# VHDCI.net
KiCad netlist of a schematic drawn in Altium Designer
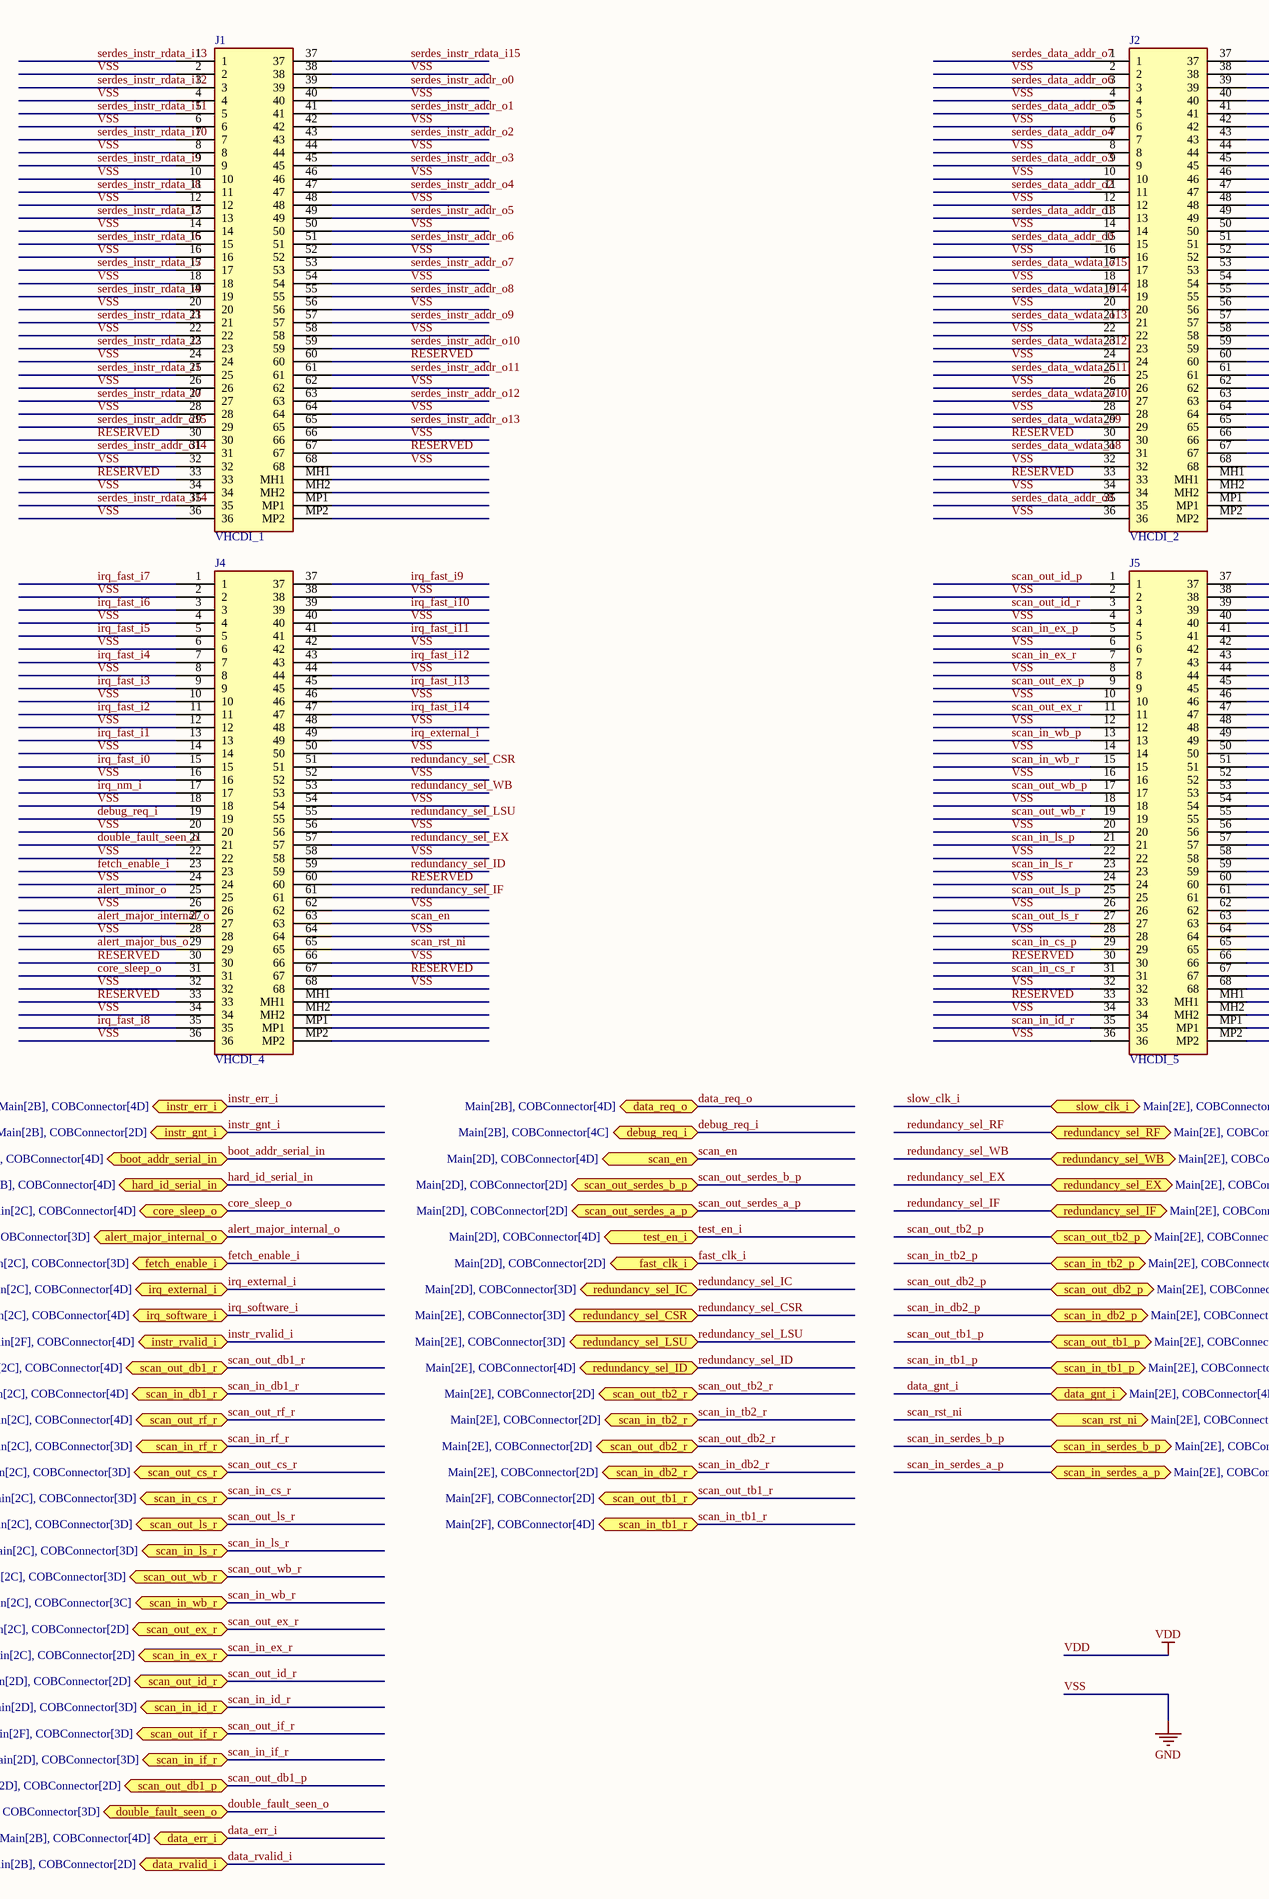
[diagram p0: VHDCI.SchDoc, left]
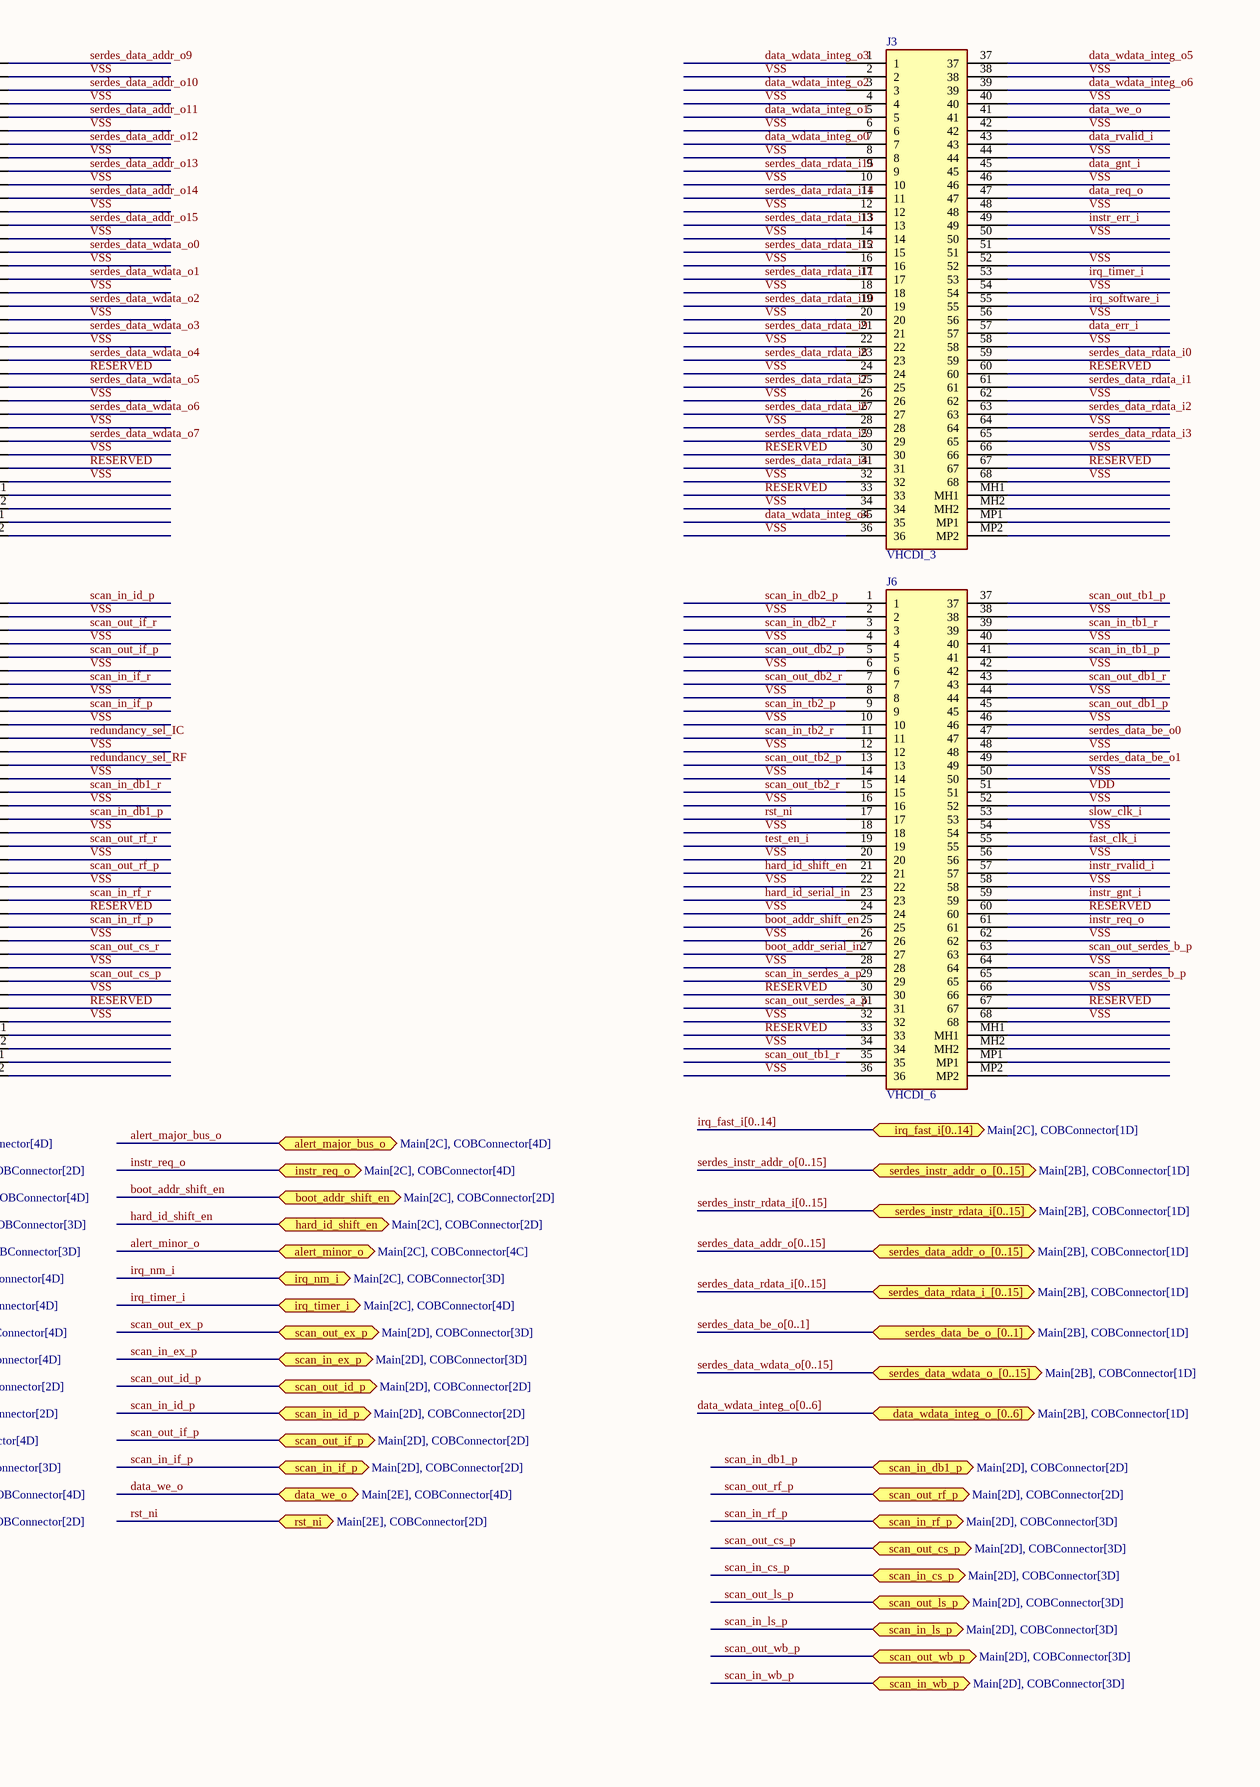
[diagram p1: VHDCI.SchDoc, right]

(export (version "E")
  (design (tool "Eeschema 10.0.6"))
  (components
    (comp (ref "J1")
      (value "VHCDI_1")
      (footprint "CONN68_HDRA-EC_HON")
      (description "Connector")
      (fields (field (name "MANUFACTURER_PART_NUMBER") "785633-01"))
      (libsource (lib "00-100001-001") (part "785633-01"))
    )
    (comp (ref "J2")
      (value "VHCDI_2")
      (footprint "CONN68_HDRA-EC_HON")
      (description "Connector")
      (fields (field (name "MANUFACTURER_PART_NUMBER") "785633-01"))
      (libsource (lib "00-100001-001") (part "785633-01"))
    )
    (comp (ref "J3")
      (value "VHCDI_3")
      (footprint "CONN68_HDRA-EC_HON")
      (description "Connector")
      (fields (field (name "MANUFACTURER_PART_NUMBER") "785633-01"))
      (libsource (lib "00-100001-001") (part "785633-01"))
    )
    (comp (ref "J4")
      (value "VHCDI_4")
      (footprint "CONN68_HDRA-EC_HON")
      (description "Connector")
      (fields (field (name "MANUFACTURER_PART_NUMBER") "785633-01"))
      (libsource (lib "00-100001-001") (part "785633-01"))
    )
    (comp (ref "J5")
      (value "VHCDI_5")
      (footprint "CONN68_HDRA-EC_HON")
      (description "Connector")
      (fields (field (name "MANUFACTURER_PART_NUMBER") "785633-01"))
      (libsource (lib "00-100001-001") (part "785633-01"))
    )
    (comp (ref "J6")
      (value "VHCDI_6")
      (footprint "CONN68_HDRA-EC_HON")
      (description "Connector")
      (fields (field (name "MANUFACTURER_PART_NUMBER") "785633-01"))
      (libsource (lib "00-100001-001") (part "785633-01"))
    )
  )
  (nets
    (net (code "1") (name "/RESERVED") (class "Default")
      (node (ref "J1") (pin "30") (pinfunction "30_30") (pintype "passive"))
      (node (ref "J1") (pin "33") (pinfunction "33_33") (pintype "passive"))
      (node (ref "J1") (pin "60") (pinfunction "60_60") (pintype "passive"))
      (node (ref "J1") (pin "67") (pinfunction "67_67") (pintype "passive"))
      (node (ref "J2") (pin "30") (pinfunction "30_30") (pintype "passive"))
      (node (ref "J2") (pin "33") (pinfunction "33_33") (pintype "passive"))
      (node (ref "J2") (pin "60") (pinfunction "60_60") (pintype "passive"))
      (node (ref "J2") (pin "67") (pinfunction "67_67") (pintype "passive"))
      (node (ref "J3") (pin "30") (pinfunction "30_30") (pintype "passive"))
      (node (ref "J3") (pin "33") (pinfunction "33_33") (pintype "passive"))
      (node (ref "J3") (pin "60") (pinfunction "60_60") (pintype "passive"))
      (node (ref "J3") (pin "67") (pinfunction "67_67") (pintype "passive"))
      (node (ref "J4") (pin "30") (pinfunction "30_30") (pintype "passive"))
      (node (ref "J4") (pin "33") (pinfunction "33_33") (pintype "passive"))
      (node (ref "J4") (pin "60") (pinfunction "60_60") (pintype "passive"))
      (node (ref "J4") (pin "67") (pinfunction "67_67") (pintype "passive"))
      (node (ref "J5") (pin "30") (pinfunction "30_30") (pintype "passive"))
      (node (ref "J5") (pin "33") (pinfunction "33_33") (pintype "passive"))
      (node (ref "J5") (pin "60") (pinfunction "60_60") (pintype "passive"))
      (node (ref "J5") (pin "67") (pinfunction "67_67") (pintype "passive"))
      (node (ref "J6") (pin "30") (pinfunction "30_30") (pintype "passive"))
      (node (ref "J6") (pin "33") (pinfunction "33_33") (pintype "passive"))
      (node (ref "J6") (pin "60") (pinfunction "60_60") (pintype "passive"))
      (node (ref "J6") (pin "67") (pinfunction "67_67") (pintype "passive"))
    )
    (net (code "2") (name "/alert_major_bus_o") (class "Default")
      (node (ref "J4") (pin "29") (pinfunction "29_29") (pintype "passive"))
    )
    (net (code "3") (name "/alert_major_internal_o") (class "Default")
      (node (ref "J4") (pin "27") (pinfunction "27_27") (pintype "passive"))
    )
    (net (code "4") (name "/alert_minor_o") (class "Default")
      (node (ref "J4") (pin "25") (pinfunction "25_25") (pintype "passive"))
    )
    (net (code "5") (name "/boot_addr_serial_in") (class "Default")
      (node (ref "J6") (pin "27") (pinfunction "27_27") (pintype "passive"))
    )
    (net (code "6") (name "/boot_addr_shift_en") (class "Default")
      (node (ref "J6") (pin "25") (pinfunction "25_25") (pintype "passive"))
    )
    (net (code "7") (name "/core_sleep_o") (class "Default")
      (node (ref "J4") (pin "31") (pinfunction "31_31") (pintype "passive"))
    )
    (net (code "8") (name "/data_err_i") (class "Default")
      (node (ref "J3") (pin "57") (pinfunction "57_57") (pintype "passive"))
    )
    (net (code "9") (name "/data_gnt_i") (class "Default")
      (node (ref "J3") (pin "45") (pinfunction "45_45") (pintype "passive"))
    )
    (net (code "10") (name "/data_req_o") (class "Default")
      (node (ref "J3") (pin "47") (pinfunction "47_47") (pintype "passive"))
    )
    (net (code "11") (name "/data_rvalid_i") (class "Default")
      (node (ref "J3") (pin "43") (pinfunction "43_43") (pintype "passive"))
    )
    (net (code "12") (name "/data_wdata_integ_o0") (class "Default")
      (node (ref "J3") (pin "7") (pinfunction "7_7") (pintype "passive"))
    )
    (net (code "13") (name "/data_wdata_integ_o1") (class "Default")
      (node (ref "J3") (pin "5") (pinfunction "5_5") (pintype "passive"))
    )
    (net (code "14") (name "/data_wdata_integ_o2") (class "Default")
      (node (ref "J3") (pin "3") (pinfunction "3_3") (pintype "passive"))
    )
    (net (code "15") (name "/data_wdata_integ_o3") (class "Default")
      (node (ref "J3") (pin "1") (pinfunction "1_1") (pintype "passive"))
    )
    (net (code "16") (name "/data_wdata_integ_o4") (class "Default")
      (node (ref "J3") (pin "35") (pinfunction "35_35") (pintype "passive"))
    )
    (net (code "17") (name "/data_wdata_integ_o5") (class "Default")
      (node (ref "J3") (pin "37") (pinfunction "37_37") (pintype "passive"))
    )
    (net (code "18") (name "/data_wdata_integ_o6") (class "Default")
      (node (ref "J3") (pin "39") (pinfunction "39_39") (pintype "passive"))
    )
    (net (code "20") (name "/data_we_o") (class "Default")
      (node (ref "J3") (pin "41") (pinfunction "41_41") (pintype "passive"))
    )
    (net (code "21") (name "/debug_req_i") (class "Default")
      (node (ref "J4") (pin "19") (pinfunction "19_19") (pintype "passive"))
    )
    (net (code "22") (name "/double_fault_seen_o") (class "Default")
      (node (ref "J4") (pin "21") (pinfunction "21_21") (pintype "passive"))
    )
    (net (code "23") (name "/fast_clk_i") (class "Default")
      (node (ref "J6") (pin "55") (pinfunction "55_55") (pintype "passive"))
    )
    (net (code "24") (name "/fetch_enable_i") (class "Default")
      (node (ref "J4") (pin "23") (pinfunction "23_23") (pintype "passive"))
    )
    (net (code "25") (name "/hard_id_serial_in") (class "Default")
      (node (ref "J6") (pin "23") (pinfunction "23_23") (pintype "passive"))
    )
    (net (code "26") (name "/hard_id_shift_en") (class "Default")
      (node (ref "J6") (pin "21") (pinfunction "21_21") (pintype "passive"))
    )
    (net (code "27") (name "/instr_err_i") (class "Default")
      (node (ref "J3") (pin "49") (pinfunction "49_49") (pintype "passive"))
    )
    (net (code "28") (name "/instr_gnt_i") (class "Default")
      (node (ref "J6") (pin "59") (pinfunction "59_59") (pintype "passive"))
    )
    (net (code "29") (name "/instr_req_o") (class "Default")
      (node (ref "J6") (pin "61") (pinfunction "61_61") (pintype "passive"))
    )
    (net (code "30") (name "/instr_rvalid_i") (class "Default")
      (node (ref "J6") (pin "57") (pinfunction "57_57") (pintype "passive"))
    )
    (net (code "31") (name "/irq_external_i") (class "Default")
      (node (ref "J4") (pin "49") (pinfunction "49_49") (pintype "passive"))
    )
    (net (code "32") (name "/irq_fast_i0") (class "Default")
      (node (ref "J4") (pin "15") (pinfunction "15_15") (pintype "passive"))
    )
    (net (code "33") (name "/irq_fast_i1") (class "Default")
      (node (ref "J4") (pin "13") (pinfunction "13_13") (pintype "passive"))
    )
    (net (code "34") (name "/irq_fast_i2") (class "Default")
      (node (ref "J4") (pin "11") (pinfunction "11_11") (pintype "passive"))
    )
    (net (code "35") (name "/irq_fast_i3") (class "Default")
      (node (ref "J4") (pin "9") (pinfunction "9_9") (pintype "passive"))
    )
    (net (code "36") (name "/irq_fast_i4") (class "Default")
      (node (ref "J4") (pin "7") (pinfunction "7_7") (pintype "passive"))
    )
    (net (code "37") (name "/irq_fast_i5") (class "Default")
      (node (ref "J4") (pin "5") (pinfunction "5_5") (pintype "passive"))
    )
    (net (code "38") (name "/irq_fast_i6") (class "Default")
      (node (ref "J4") (pin "3") (pinfunction "3_3") (pintype "passive"))
    )
    (net (code "39") (name "/irq_fast_i7") (class "Default")
      (node (ref "J4") (pin "1") (pinfunction "1_1") (pintype "passive"))
    )
    (net (code "40") (name "/irq_fast_i8") (class "Default")
      (node (ref "J4") (pin "35") (pinfunction "35_35") (pintype "passive"))
    )
    (net (code "41") (name "/irq_fast_i9") (class "Default")
      (node (ref "J4") (pin "37") (pinfunction "37_37") (pintype "passive"))
    )
    (net (code "42") (name "/irq_fast_i10") (class "Default")
      (node (ref "J4") (pin "39") (pinfunction "39_39") (pintype "passive"))
    )
    (net (code "43") (name "/irq_fast_i11") (class "Default")
      (node (ref "J4") (pin "41") (pinfunction "41_41") (pintype "passive"))
    )
    (net (code "44") (name "/irq_fast_i12") (class "Default")
      (node (ref "J4") (pin "43") (pinfunction "43_43") (pintype "passive"))
    )
    (net (code "45") (name "/irq_fast_i13") (class "Default")
      (node (ref "J4") (pin "45") (pinfunction "45_45") (pintype "passive"))
    )
    (net (code "46") (name "/irq_fast_i14") (class "Default")
      (node (ref "J4") (pin "47") (pinfunction "47_47") (pintype "passive"))
    )
    (net (code "48") (name "/irq_nm_i") (class "Default")
      (node (ref "J4") (pin "17") (pinfunction "17_17") (pintype "passive"))
    )
    (net (code "49") (name "/irq_software_i") (class "Default")
      (node (ref "J3") (pin "55") (pinfunction "55_55") (pintype "passive"))
    )
    (net (code "50") (name "/irq_timer_i") (class "Default")
      (node (ref "J3") (pin "53") (pinfunction "53_53") (pintype "passive"))
    )
    (net (code "51") (name "/redundancy_sel_CSR") (class "Default")
      (node (ref "J4") (pin "51") (pinfunction "51_51") (pintype "passive"))
    )
    (net (code "52") (name "/redundancy_sel_EX") (class "Default")
      (node (ref "J4") (pin "57") (pinfunction "57_57") (pintype "passive"))
    )
    (net (code "53") (name "/redundancy_sel_IC") (class "Default")
      (node (ref "J5") (pin "47") (pinfunction "47_47") (pintype "passive"))
    )
    (net (code "54") (name "/redundancy_sel_ID") (class "Default")
      (node (ref "J4") (pin "59") (pinfunction "59_59") (pintype "passive"))
    )
    (net (code "55") (name "/redundancy_sel_IF") (class "Default")
      (node (ref "J4") (pin "61") (pinfunction "61_61") (pintype "passive"))
    )
    (net (code "56") (name "/redundancy_sel_LSU") (class "Default")
      (node (ref "J4") (pin "55") (pinfunction "55_55") (pintype "passive"))
    )
    (net (code "57") (name "/redundancy_sel_RF") (class "Default")
      (node (ref "J5") (pin "49") (pinfunction "49_49") (pintype "passive"))
    )
    (net (code "58") (name "/redundancy_sel_WB") (class "Default")
      (node (ref "J4") (pin "53") (pinfunction "53_53") (pintype "passive"))
    )
    (net (code "59") (name "/rst_ni") (class "Default")
      (node (ref "J6") (pin "17") (pinfunction "17_17") (pintype "passive"))
    )
    (net (code "60") (name "/scan_en") (class "Default")
      (node (ref "J4") (pin "63") (pinfunction "63_63") (pintype "passive"))
    )
    (net (code "61") (name "/scan_in_cs_p") (class "Default")
      (node (ref "J5") (pin "29") (pinfunction "29_29") (pintype "passive"))
    )
    (net (code "62") (name "/scan_in_cs_r") (class "Default")
      (node (ref "J5") (pin "31") (pinfunction "31_31") (pintype "passive"))
    )
    (net (code "63") (name "/scan_in_db1_p") (class "Default")
      (node (ref "J5") (pin "53") (pinfunction "53_53") (pintype "passive"))
    )
    (net (code "64") (name "/scan_in_db1_r") (class "Default")
      (node (ref "J5") (pin "51") (pinfunction "51_51") (pintype "passive"))
    )
    (net (code "65") (name "/scan_in_db2_p") (class "Default")
      (node (ref "J6") (pin "1") (pinfunction "1_1") (pintype "passive"))
    )
    (net (code "66") (name "/scan_in_db2_r") (class "Default")
      (node (ref "J6") (pin "3") (pinfunction "3_3") (pintype "passive"))
    )
    (net (code "67") (name "/scan_in_ex_p") (class "Default")
      (node (ref "J5") (pin "5") (pinfunction "5_5") (pintype "passive"))
    )
    (net (code "68") (name "/scan_in_ex_r") (class "Default")
      (node (ref "J5") (pin "7") (pinfunction "7_7") (pintype "passive"))
    )
    (net (code "69") (name "/scan_in_id_p") (class "Default")
      (node (ref "J5") (pin "37") (pinfunction "37_37") (pintype "passive"))
    )
    (net (code "70") (name "/scan_in_id_r") (class "Default")
      (node (ref "J5") (pin "35") (pinfunction "35_35") (pintype "passive"))
    )
    (net (code "71") (name "/scan_in_if_p") (class "Default")
      (node (ref "J5") (pin "45") (pinfunction "45_45") (pintype "passive"))
    )
    (net (code "72") (name "/scan_in_if_r") (class "Default")
      (node (ref "J5") (pin "43") (pinfunction "43_43") (pintype "passive"))
    )
    (net (code "73") (name "/scan_in_ls_p") (class "Default")
      (node (ref "J5") (pin "21") (pinfunction "21_21") (pintype "passive"))
    )
    (net (code "74") (name "/scan_in_ls_r") (class "Default")
      (node (ref "J5") (pin "23") (pinfunction "23_23") (pintype "passive"))
    )
    (net (code "75") (name "/scan_in_rf_p") (class "Default")
      (node (ref "J5") (pin "61") (pinfunction "61_61") (pintype "passive"))
    )
    (net (code "76") (name "/scan_in_rf_r") (class "Default")
      (node (ref "J5") (pin "59") (pinfunction "59_59") (pintype "passive"))
    )
    (net (code "77") (name "/scan_in_serdes_a_p") (class "Default")
      (node (ref "J6") (pin "29") (pinfunction "29_29") (pintype "passive"))
    )
    (net (code "78") (name "/scan_in_serdes_b_p") (class "Default")
      (node (ref "J6") (pin "65") (pinfunction "65_65") (pintype "passive"))
    )
    (net (code "79") (name "/scan_in_tb1_p") (class "Default")
      (node (ref "J6") (pin "41") (pinfunction "41_41") (pintype "passive"))
    )
    (net (code "80") (name "/scan_in_tb1_r") (class "Default")
      (node (ref "J6") (pin "39") (pinfunction "39_39") (pintype "passive"))
    )
    (net (code "81") (name "/scan_in_tb2_p") (class "Default")
      (node (ref "J6") (pin "9") (pinfunction "9_9") (pintype "passive"))
    )
    (net (code "82") (name "/scan_in_tb2_r") (class "Default")
      (node (ref "J6") (pin "11") (pinfunction "11_11") (pintype "passive"))
    )
    (net (code "83") (name "/scan_in_wb_p") (class "Default")
      (node (ref "J5") (pin "13") (pinfunction "13_13") (pintype "passive"))
    )
    (net (code "84") (name "/scan_in_wb_r") (class "Default")
      (node (ref "J5") (pin "15") (pinfunction "15_15") (pintype "passive"))
    )
    (net (code "85") (name "/scan_out_cs_p") (class "Default")
      (node (ref "J5") (pin "65") (pinfunction "65_65") (pintype "passive"))
    )
    (net (code "86") (name "/scan_out_cs_r") (class "Default")
      (node (ref "J5") (pin "63") (pinfunction "63_63") (pintype "passive"))
    )
    (net (code "87") (name "/scan_out_db1_p") (class "Default")
      (node (ref "J6") (pin "45") (pinfunction "45_45") (pintype "passive"))
    )
    (net (code "88") (name "/scan_out_db1_r") (class "Default")
      (node (ref "J6") (pin "43") (pinfunction "43_43") (pintype "passive"))
    )
    (net (code "89") (name "/scan_out_db2_p") (class "Default")
      (node (ref "J6") (pin "5") (pinfunction "5_5") (pintype "passive"))
    )
    (net (code "90") (name "/scan_out_db2_r") (class "Default")
      (node (ref "J6") (pin "7") (pinfunction "7_7") (pintype "passive"))
    )
    (net (code "91") (name "/scan_out_ex_p") (class "Default")
      (node (ref "J5") (pin "9") (pinfunction "9_9") (pintype "passive"))
    )
    (net (code "92") (name "/scan_out_ex_r") (class "Default")
      (node (ref "J5") (pin "11") (pinfunction "11_11") (pintype "passive"))
    )
    (net (code "93") (name "/scan_out_id_p") (class "Default")
      (node (ref "J5") (pin "1") (pinfunction "1_1") (pintype "passive"))
    )
    (net (code "94") (name "/scan_out_id_r") (class "Default")
      (node (ref "J5") (pin "3") (pinfunction "3_3") (pintype "passive"))
    )
    (net (code "95") (name "/scan_out_if_p") (class "Default")
      (node (ref "J5") (pin "41") (pinfunction "41_41") (pintype "passive"))
    )
    (net (code "96") (name "/scan_out_if_r") (class "Default")
      (node (ref "J5") (pin "39") (pinfunction "39_39") (pintype "passive"))
    )
    (net (code "97") (name "/scan_out_ls_p") (class "Default")
      (node (ref "J5") (pin "25") (pinfunction "25_25") (pintype "passive"))
    )
    (net (code "98") (name "/scan_out_ls_r") (class "Default")
      (node (ref "J5") (pin "27") (pinfunction "27_27") (pintype "passive"))
    )
    (net (code "99") (name "/scan_out_rf_p") (class "Default")
      (node (ref "J5") (pin "57") (pinfunction "57_57") (pintype "passive"))
    )
    (net (code "100") (name "/scan_out_rf_r") (class "Default")
      (node (ref "J5") (pin "55") (pinfunction "55_55") (pintype "passive"))
    )
    (net (code "101") (name "/scan_out_serdes_a_p") (class "Default")
      (node (ref "J6") (pin "31") (pinfunction "31_31") (pintype "passive"))
    )
    (net (code "102") (name "/scan_out_serdes_b_p") (class "Default")
      (node (ref "J6") (pin "63") (pinfunction "63_63") (pintype "passive"))
    )
    (net (code "103") (name "/scan_out_tb1_p") (class "Default")
      (node (ref "J6") (pin "37") (pinfunction "37_37") (pintype "passive"))
    )
    (net (code "104") (name "/scan_out_tb1_r") (class "Default")
      (node (ref "J6") (pin "35") (pinfunction "35_35") (pintype "passive"))
    )
    (net (code "105") (name "/scan_out_tb2_p") (class "Default")
      (node (ref "J6") (pin "13") (pinfunction "13_13") (pintype "passive"))
    )
    (net (code "106") (name "/scan_out_tb2_r") (class "Default")
      (node (ref "J6") (pin "15") (pinfunction "15_15") (pintype "passive"))
    )
    (net (code "107") (name "/scan_out_wb_p") (class "Default")
      (node (ref "J5") (pin "17") (pinfunction "17_17") (pintype "passive"))
    )
    (net (code "108") (name "/scan_out_wb_r") (class "Default")
      (node (ref "J5") (pin "19") (pinfunction "19_19") (pintype "passive"))
    )
    (net (code "109") (name "/scan_rst_ni") (class "Default")
      (node (ref "J4") (pin "65") (pinfunction "65_65") (pintype "passive"))
    )
    (net (code "110") (name "/serdes_data_addr_o0") (class "Default")
      (node (ref "J2") (pin "15") (pinfunction "15_15") (pintype "passive"))
    )
    (net (code "111") (name "/serdes_data_addr_o1") (class "Default")
      (node (ref "J2") (pin "13") (pinfunction "13_13") (pintype "passive"))
    )
    (net (code "112") (name "/serdes_data_addr_o2") (class "Default")
      (node (ref "J2") (pin "11") (pinfunction "11_11") (pintype "passive"))
    )
    (net (code "113") (name "/serdes_data_addr_o3") (class "Default")
      (node (ref "J2") (pin "9") (pinfunction "9_9") (pintype "passive"))
    )
    (net (code "114") (name "/serdes_data_addr_o4") (class "Default")
      (node (ref "J2") (pin "7") (pinfunction "7_7") (pintype "passive"))
    )
    (net (code "115") (name "/serdes_data_addr_o5") (class "Default")
      (node (ref "J2") (pin "5") (pinfunction "5_5") (pintype "passive"))
    )
    (net (code "116") (name "/serdes_data_addr_o6") (class "Default")
      (node (ref "J2") (pin "3") (pinfunction "3_3") (pintype "passive"))
    )
    (net (code "117") (name "/serdes_data_addr_o7") (class "Default")
      (node (ref "J2") (pin "1") (pinfunction "1_1") (pintype "passive"))
    )
    (net (code "118") (name "/serdes_data_addr_o8") (class "Default")
      (node (ref "J2") (pin "35") (pinfunction "35_35") (pintype "passive"))
    )
    (net (code "119") (name "/serdes_data_addr_o9") (class "Default")
      (node (ref "J2") (pin "37") (pinfunction "37_37") (pintype "passive"))
    )
    (net (code "120") (name "/serdes_data_addr_o10") (class "Default")
      (node (ref "J2") (pin "39") (pinfunction "39_39") (pintype "passive"))
    )
    (net (code "121") (name "/serdes_data_addr_o11") (class "Default")
      (node (ref "J2") (pin "41") (pinfunction "41_41") (pintype "passive"))
    )
    (net (code "122") (name "/serdes_data_addr_o12") (class "Default")
      (node (ref "J2") (pin "43") (pinfunction "43_43") (pintype "passive"))
    )
    (net (code "123") (name "/serdes_data_addr_o13") (class "Default")
      (node (ref "J2") (pin "45") (pinfunction "45_45") (pintype "passive"))
    )
    (net (code "124") (name "/serdes_data_addr_o14") (class "Default")
      (node (ref "J2") (pin "47") (pinfunction "47_47") (pintype "passive"))
    )
    (net (code "125") (name "/serdes_data_addr_o15") (class "Default")
      (node (ref "J2") (pin "49") (pinfunction "49_49") (pintype "passive"))
    )
    (net (code "127") (name "/serdes_data_be_o0") (class "Default")
      (node (ref "J6") (pin "47") (pinfunction "47_47") (pintype "passive"))
    )
    (net (code "128") (name "/serdes_data_be_o1") (class "Default")
      (node (ref "J6") (pin "49") (pinfunction "49_49") (pintype "passive"))
    )
    (net (code "130") (name "/serdes_data_rdata_i0") (class "Default")
      (node (ref "J3") (pin "59") (pinfunction "59_59") (pintype "passive"))
    )
    (net (code "131") (name "/serdes_data_rdata_i1") (class "Default")
      (node (ref "J3") (pin "61") (pinfunction "61_61") (pintype "passive"))
    )
    (net (code "132") (name "/serdes_data_rdata_i2") (class "Default")
      (node (ref "J3") (pin "63") (pinfunction "63_63") (pintype "passive"))
    )
    (net (code "133") (name "/serdes_data_rdata_i3") (class "Default")
      (node (ref "J3") (pin "65") (pinfunction "65_65") (pintype "passive"))
    )
    (net (code "134") (name "/serdes_data_rdata_i4") (class "Default")
      (node (ref "J3") (pin "31") (pinfunction "31_31") (pintype "passive"))
    )
    (net (code "135") (name "/serdes_data_rdata_i5") (class "Default")
      (node (ref "J3") (pin "29") (pinfunction "29_29") (pintype "passive"))
    )
    (net (code "136") (name "/serdes_data_rdata_i6") (class "Default")
      (node (ref "J3") (pin "27") (pinfunction "27_27") (pintype "passive"))
    )
    (net (code "137") (name "/serdes_data_rdata_i7") (class "Default")
      (node (ref "J3") (pin "25") (pinfunction "25_25") (pintype "passive"))
    )
    (net (code "138") (name "/serdes_data_rdata_i8") (class "Default")
      (node (ref "J3") (pin "23") (pinfunction "23_23") (pintype "passive"))
    )
    (net (code "139") (name "/serdes_data_rdata_i9") (class "Default")
      (node (ref "J3") (pin "21") (pinfunction "21_21") (pintype "passive"))
    )
    (net (code "140") (name "/serdes_data_rdata_i10") (class "Default")
      (node (ref "J3") (pin "19") (pinfunction "19_19") (pintype "passive"))
    )
    (net (code "141") (name "/serdes_data_rdata_i11") (class "Default")
      (node (ref "J3") (pin "17") (pinfunction "17_17") (pintype "passive"))
    )
    (net (code "142") (name "/serdes_data_rdata_i12") (class "Default")
      (node (ref "J3") (pin "15") (pinfunction "15_15") (pintype "passive"))
    )
    (net (code "143") (name "/serdes_data_rdata_i13") (class "Default")
      (node (ref "J3") (pin "13") (pinfunction "13_13") (pintype "passive"))
    )
    (net (code "144") (name "/serdes_data_rdata_i14") (class "Default")
      (node (ref "J3") (pin "11") (pinfunction "11_11") (pintype "passive"))
    )
    (net (code "145") (name "/serdes_data_rdata_i15") (class "Default")
      (node (ref "J3") (pin "9") (pinfunction "9_9") (pintype "passive"))
    )
    (net (code "147") (name "/serdes_data_wdata_o0") (class "Default")
      (node (ref "J2") (pin "51") (pinfunction "51_51") (pintype "passive"))
    )
    (net (code "148") (name "/serdes_data_wdata_o1") (class "Default")
      (node (ref "J2") (pin "53") (pinfunction "53_53") (pintype "passive"))
    )
    (net (code "149") (name "/serdes_data_wdata_o2") (class "Default")
      (node (ref "J2") (pin "55") (pinfunction "55_55") (pintype "passive"))
    )
    (net (code "150") (name "/serdes_data_wdata_o3") (class "Default")
      (node (ref "J2") (pin "57") (pinfunction "57_57") (pintype "passive"))
    )
    (net (code "151") (name "/serdes_data_wdata_o4") (class "Default")
      (node (ref "J2") (pin "59") (pinfunction "59_59") (pintype "passive"))
    )
    (net (code "152") (name "/serdes_data_wdata_o5") (class "Default")
      (node (ref "J2") (pin "61") (pinfunction "61_61") (pintype "passive"))
    )
    (net (code "153") (name "/serdes_data_wdata_o6") (class "Default")
      (node (ref "J2") (pin "63") (pinfunction "63_63") (pintype "passive"))
    )
    (net (code "154") (name "/serdes_data_wdata_o7") (class "Default")
      (node (ref "J2") (pin "65") (pinfunction "65_65") (pintype "passive"))
    )
    (net (code "155") (name "/serdes_data_wdata_o8") (class "Default")
      (node (ref "J2") (pin "31") (pinfunction "31_31") (pintype "passive"))
    )
    (net (code "156") (name "/serdes_data_wdata_o9") (class "Default")
      (node (ref "J2") (pin "29") (pinfunction "29_29") (pintype "passive"))
    )
    (net (code "157") (name "/serdes_data_wdata_o10") (class "Default")
      (node (ref "J2") (pin "27") (pinfunction "27_27") (pintype "passive"))
    )
    (net (code "158") (name "/serdes_data_wdata_o11") (class "Default")
      (node (ref "J2") (pin "25") (pinfunction "25_25") (pintype "passive"))
    )
    (net (code "159") (name "/serdes_data_wdata_o12") (class "Default")
      (node (ref "J2") (pin "23") (pinfunction "23_23") (pintype "passive"))
    )
    (net (code "160") (name "/serdes_data_wdata_o13") (class "Default")
      (node (ref "J2") (pin "21") (pinfunction "21_21") (pintype "passive"))
    )
    (net (code "161") (name "/serdes_data_wdata_o14") (class "Default")
      (node (ref "J2") (pin "19") (pinfunction "19_19") (pintype "passive"))
    )
    (net (code "162") (name "/serdes_data_wdata_o15") (class "Default")
      (node (ref "J2") (pin "17") (pinfunction "17_17") (pintype "passive"))
    )
    (net (code "164") (name "/serdes_instr_addr_o0") (class "Default")
      (node (ref "J1") (pin "39") (pinfunction "39_39") (pintype "passive"))
    )
    (net (code "165") (name "/serdes_instr_addr_o1") (class "Default")
      (node (ref "J1") (pin "41") (pinfunction "41_41") (pintype "passive"))
    )
    (net (code "166") (name "/serdes_instr_addr_o2") (class "Default")
      (node (ref "J1") (pin "43") (pinfunction "43_43") (pintype "passive"))
    )
    (net (code "167") (name "/serdes_instr_addr_o3") (class "Default")
      (node (ref "J1") (pin "45") (pinfunction "45_45") (pintype "passive"))
    )
    (net (code "168") (name "/serdes_instr_addr_o4") (class "Default")
      (node (ref "J1") (pin "47") (pinfunction "47_47") (pintype "passive"))
    )
    (net (code "169") (name "/serdes_instr_addr_o5") (class "Default")
      (node (ref "J1") (pin "49") (pinfunction "49_49") (pintype "passive"))
    )
    (net (code "170") (name "/serdes_instr_addr_o6") (class "Default")
      (node (ref "J1") (pin "51") (pinfunction "51_51") (pintype "passive"))
    )
    (net (code "171") (name "/serdes_instr_addr_o7") (class "Default")
      (node (ref "J1") (pin "53") (pinfunction "53_53") (pintype "passive"))
    )
    (net (code "172") (name "/serdes_instr_addr_o8") (class "Default")
      (node (ref "J1") (pin "55") (pinfunction "55_55") (pintype "passive"))
    )
    (net (code "173") (name "/serdes_instr_addr_o9") (class "Default")
      (node (ref "J1") (pin "57") (pinfunction "57_57") (pintype "passive"))
    )
    (net (code "174") (name "/serdes_instr_addr_o10") (class "Default")
      (node (ref "J1") (pin "59") (pinfunction "59_59") (pintype "passive"))
    )
    (net (code "175") (name "/serdes_instr_addr_o11") (class "Default")
      (node (ref "J1") (pin "61") (pinfunction "61_61") (pintype "passive"))
    )
    (net (code "176") (name "/serdes_instr_addr_o12") (class "Default")
      (node (ref "J1") (pin "63") (pinfunction "63_63") (pintype "passive"))
    )
    (net (code "177") (name "/serdes_instr_addr_o13") (class "Default")
      (node (ref "J1") (pin "65") (pinfunction "65_65") (pintype "passive"))
    )
    (net (code "178") (name "/serdes_instr_addr_o14") (class "Default")
      (node (ref "J1") (pin "31") (pinfunction "31_31") (pintype "passive"))
    )
    (net (code "179") (name "/serdes_instr_addr_o15") (class "Default")
      (node (ref "J1") (pin "29") (pinfunction "29_29") (pintype "passive"))
    )
    (net (code "181") (name "/serdes_instr_rdata_i0") (class "Default")
      (node (ref "J1") (pin "27") (pinfunction "27_27") (pintype "passive"))
    )
    (net (code "182") (name "/serdes_instr_rdata_i1") (class "Default")
      (node (ref "J1") (pin "25") (pinfunction "25_25") (pintype "passive"))
    )
    (net (code "183") (name "/serdes_instr_rdata_i2") (class "Default")
      (node (ref "J1") (pin "23") (pinfunction "23_23") (pintype "passive"))
    )
    (net (code "184") (name "/serdes_instr_rdata_i3") (class "Default")
      (node (ref "J1") (pin "21") (pinfunction "21_21") (pintype "passive"))
    )
    (net (code "185") (name "/serdes_instr_rdata_i4") (class "Default")
      (node (ref "J1") (pin "19") (pinfunction "19_19") (pintype "passive"))
    )
    (net (code "186") (name "/serdes_instr_rdata_i5") (class "Default")
      (node (ref "J1") (pin "17") (pinfunction "17_17") (pintype "passive"))
    )
    (net (code "187") (name "/serdes_instr_rdata_i6") (class "Default")
      (node (ref "J1") (pin "15") (pinfunction "15_15") (pintype "passive"))
    )
    (net (code "188") (name "/serdes_instr_rdata_i7") (class "Default")
      (node (ref "J1") (pin "13") (pinfunction "13_13") (pintype "passive"))
    )
    (net (code "189") (name "/serdes_instr_rdata_i8") (class "Default")
      (node (ref "J1") (pin "11") (pinfunction "11_11") (pintype "passive"))
    )
    (net (code "190") (name "/serdes_instr_rdata_i9") (class "Default")
      (node (ref "J1") (pin "9") (pinfunction "9_9") (pintype "passive"))
    )
    (net (code "191") (name "/serdes_instr_rdata_i10") (class "Default")
      (node (ref "J1") (pin "7") (pinfunction "7_7") (pintype "passive"))
    )
    (net (code "192") (name "/serdes_instr_rdata_i11") (class "Default")
      (node (ref "J1") (pin "5") (pinfunction "5_5") (pintype "passive"))
    )
    (net (code "193") (name "/serdes_instr_rdata_i12") (class "Default")
      (node (ref "J1") (pin "3") (pinfunction "3_3") (pintype "passive"))
    )
    (net (code "194") (name "/serdes_instr_rdata_i13") (class "Default")
      (node (ref "J1") (pin "1") (pinfunction "1_1") (pintype "passive"))
    )
    (net (code "195") (name "/serdes_instr_rdata_i14") (class "Default")
      (node (ref "J1") (pin "35") (pinfunction "35_35") (pintype "passive"))
    )
    (net (code "196") (name "/serdes_instr_rdata_i15") (class "Default")
      (node (ref "J1") (pin "37") (pinfunction "37_37") (pintype "passive"))
    )
    (net (code "198") (name "/slow_clk_i") (class "Default")
      (node (ref "J6") (pin "53") (pinfunction "53_53") (pintype "passive"))
    )
    (net (code "199") (name "/test_en_i") (class "Default")
      (node (ref "J6") (pin "19") (pinfunction "19_19") (pintype "passive"))
    )
    (net (code "200") (name "GND") (class "Default")
      (node (ref "J1") (pin "10") (pinfunction "10_10") (pintype "passive"))
      (node (ref "J1") (pin "12") (pinfunction "12_12") (pintype "passive"))
      (node (ref "J1") (pin "14") (pinfunction "14_14") (pintype "passive"))
      (node (ref "J1") (pin "16") (pinfunction "16_16") (pintype "passive"))
      (node (ref "J1") (pin "18") (pinfunction "18_18") (pintype "passive"))
      (node (ref "J1") (pin "2") (pinfunction "2_2") (pintype "passive"))
      (node (ref "J1") (pin "20") (pinfunction "20_20") (pintype "passive"))
      (node (ref "J1") (pin "22") (pinfunction "22_22") (pintype "passive"))
      (node (ref "J1") (pin "24") (pinfunction "24_24") (pintype "passive"))
      (node (ref "J1") (pin "26") (pinfunction "26_26") (pintype "passive"))
      (node (ref "J1") (pin "28") (pinfunction "28_28") (pintype "passive"))
      (node (ref "J1") (pin "32") (pinfunction "32_32") (pintype "passive"))
      (node (ref "J1") (pin "34") (pinfunction "34_34") (pintype "passive"))
      (node (ref "J1") (pin "36") (pinfunction "36_36") (pintype "passive"))
      (node (ref "J1") (pin "38") (pinfunction "38_38") (pintype "passive"))
      (node (ref "J1") (pin "4") (pinfunction "4_4") (pintype "passive"))
      (node (ref "J1") (pin "40") (pinfunction "40_40") (pintype "passive"))
      (node (ref "J1") (pin "42") (pinfunction "42_42") (pintype "passive"))
      (node (ref "J1") (pin "44") (pinfunction "44_44") (pintype "passive"))
      (node (ref "J1") (pin "46") (pinfunction "46_46") (pintype "passive"))
      (node (ref "J1") (pin "48") (pinfunction "48_48") (pintype "passive"))
      (node (ref "J1") (pin "50") (pinfunction "50_50") (pintype "passive"))
      (node (ref "J1") (pin "52") (pinfunction "52_52") (pintype "passive"))
      (node (ref "J1") (pin "54") (pinfunction "54_54") (pintype "passive"))
      (node (ref "J1") (pin "56") (pinfunction "56_56") (pintype "passive"))
      (node (ref "J1") (pin "58") (pinfunction "58_58") (pintype "passive"))
      (node (ref "J1") (pin "6") (pinfunction "6_6") (pintype "passive"))
      (node (ref "J1") (pin "62") (pinfunction "62_62") (pintype "passive"))
      (node (ref "J1") (pin "64") (pinfunction "64_64") (pintype "passive"))
      (node (ref "J1") (pin "66") (pinfunction "66_66") (pintype "passive"))
      (node (ref "J1") (pin "68") (pinfunction "68_68") (pintype "passive"))
      (node (ref "J1") (pin "8") (pinfunction "8_8") (pintype "passive"))
      (node (ref "J2") (pin "10") (pinfunction "10_10") (pintype "passive"))
      (node (ref "J2") (pin "12") (pinfunction "12_12") (pintype "passive"))
      (node (ref "J2") (pin "14") (pinfunction "14_14") (pintype "passive"))
      (node (ref "J2") (pin "16") (pinfunction "16_16") (pintype "passive"))
      (node (ref "J2") (pin "18") (pinfunction "18_18") (pintype "passive"))
      (node (ref "J2") (pin "2") (pinfunction "2_2") (pintype "passive"))
      (node (ref "J2") (pin "20") (pinfunction "20_20") (pintype "passive"))
      (node (ref "J2") (pin "22") (pinfunction "22_22") (pintype "passive"))
      (node (ref "J2") (pin "24") (pinfunction "24_24") (pintype "passive"))
      (node (ref "J2") (pin "26") (pinfunction "26_26") (pintype "passive"))
      (node (ref "J2") (pin "28") (pinfunction "28_28") (pintype "passive"))
      (node (ref "J2") (pin "32") (pinfunction "32_32") (pintype "passive"))
      (node (ref "J2") (pin "34") (pinfunction "34_34") (pintype "passive"))
      (node (ref "J2") (pin "36") (pinfunction "36_36") (pintype "passive"))
      (node (ref "J2") (pin "38") (pinfunction "38_38") (pintype "passive"))
      (node (ref "J2") (pin "4") (pinfunction "4_4") (pintype "passive"))
      (node (ref "J2") (pin "40") (pinfunction "40_40") (pintype "passive"))
      (node (ref "J2") (pin "42") (pinfunction "42_42") (pintype "passive"))
      (node (ref "J2") (pin "44") (pinfunction "44_44") (pintype "passive"))
      (node (ref "J2") (pin "46") (pinfunction "46_46") (pintype "passive"))
      (node (ref "J2") (pin "48") (pinfunction "48_48") (pintype "passive"))
      (node (ref "J2") (pin "50") (pinfunction "50_50") (pintype "passive"))
      (node (ref "J2") (pin "52") (pinfunction "52_52") (pintype "passive"))
      (node (ref "J2") (pin "54") (pinfunction "54_54") (pintype "passive"))
      (node (ref "J2") (pin "56") (pinfunction "56_56") (pintype "passive"))
      (node (ref "J2") (pin "58") (pinfunction "58_58") (pintype "passive"))
      (node (ref "J2") (pin "6") (pinfunction "6_6") (pintype "passive"))
      (node (ref "J2") (pin "62") (pinfunction "62_62") (pintype "passive"))
      (node (ref "J2") (pin "64") (pinfunction "64_64") (pintype "passive"))
      (node (ref "J2") (pin "66") (pinfunction "66_66") (pintype "passive"))
      (node (ref "J2") (pin "68") (pinfunction "68_68") (pintype "passive"))
      (node (ref "J2") (pin "8") (pinfunction "8_8") (pintype "passive"))
      (node (ref "J3") (pin "10") (pinfunction "10_10") (pintype "passive"))
      (node (ref "J3") (pin "12") (pinfunction "12_12") (pintype "passive"))
      (node (ref "J3") (pin "14") (pinfunction "14_14") (pintype "passive"))
      (node (ref "J3") (pin "16") (pinfunction "16_16") (pintype "passive"))
      (node (ref "J3") (pin "18") (pinfunction "18_18") (pintype "passive"))
      (node (ref "J3") (pin "2") (pinfunction "2_2") (pintype "passive"))
      (node (ref "J3") (pin "20") (pinfunction "20_20") (pintype "passive"))
      (node (ref "J3") (pin "22") (pinfunction "22_22") (pintype "passive"))
      (node (ref "J3") (pin "24") (pinfunction "24_24") (pintype "passive"))
      (node (ref "J3") (pin "26") (pinfunction "26_26") (pintype "passive"))
      (node (ref "J3") (pin "28") (pinfunction "28_28") (pintype "passive"))
      (node (ref "J3") (pin "32") (pinfunction "32_32") (pintype "passive"))
      (node (ref "J3") (pin "34") (pinfunction "34_34") (pintype "passive"))
      (node (ref "J3") (pin "36") (pinfunction "36_36") (pintype "passive"))
      (node (ref "J3") (pin "38") (pinfunction "38_38") (pintype "passive"))
      (node (ref "J3") (pin "4") (pinfunction "4_4") (pintype "passive"))
      (node (ref "J3") (pin "40") (pinfunction "40_40") (pintype "passive"))
      (node (ref "J3") (pin "42") (pinfunction "42_42") (pintype "passive"))
      (node (ref "J3") (pin "44") (pinfunction "44_44") (pintype "passive"))
      (node (ref "J3") (pin "46") (pinfunction "46_46") (pintype "passive"))
      (node (ref "J3") (pin "48") (pinfunction "48_48") (pintype "passive"))
      (node (ref "J3") (pin "50") (pinfunction "50_50") (pintype "passive"))
      (node (ref "J3") (pin "52") (pinfunction "52_52") (pintype "passive"))
      (node (ref "J3") (pin "54") (pinfunction "54_54") (pintype "passive"))
      (node (ref "J3") (pin "56") (pinfunction "56_56") (pintype "passive"))
      (node (ref "J3") (pin "58") (pinfunction "58_58") (pintype "passive"))
      (node (ref "J3") (pin "6") (pinfunction "6_6") (pintype "passive"))
      (node (ref "J3") (pin "62") (pinfunction "62_62") (pintype "passive"))
      (node (ref "J3") (pin "64") (pinfunction "64_64") (pintype "passive"))
      (node (ref "J3") (pin "66") (pinfunction "66_66") (pintype "passive"))
      (node (ref "J3") (pin "68") (pinfunction "68_68") (pintype "passive"))
      (node (ref "J3") (pin "8") (pinfunction "8_8") (pintype "passive"))
      (node (ref "J4") (pin "10") (pinfunction "10_10") (pintype "passive"))
      (node (ref "J4") (pin "12") (pinfunction "12_12") (pintype "passive"))
      (node (ref "J4") (pin "14") (pinfunction "14_14") (pintype "passive"))
      (node (ref "J4") (pin "16") (pinfunction "16_16") (pintype "passive"))
      (node (ref "J4") (pin "18") (pinfunction "18_18") (pintype "passive"))
      (node (ref "J4") (pin "2") (pinfunction "2_2") (pintype "passive"))
      (node (ref "J4") (pin "20") (pinfunction "20_20") (pintype "passive"))
      (node (ref "J4") (pin "22") (pinfunction "22_22") (pintype "passive"))
      (node (ref "J4") (pin "24") (pinfunction "24_24") (pintype "passive"))
      (node (ref "J4") (pin "26") (pinfunction "26_26") (pintype "passive"))
      (node (ref "J4") (pin "28") (pinfunction "28_28") (pintype "passive"))
      (node (ref "J4") (pin "32") (pinfunction "32_32") (pintype "passive"))
      (node (ref "J4") (pin "34") (pinfunction "34_34") (pintype "passive"))
      (node (ref "J4") (pin "36") (pinfunction "36_36") (pintype "passive"))
      (node (ref "J4") (pin "38") (pinfunction "38_38") (pintype "passive"))
      (node (ref "J4") (pin "4") (pinfunction "4_4") (pintype "passive"))
      (node (ref "J4") (pin "40") (pinfunction "40_40") (pintype "passive"))
      (node (ref "J4") (pin "42") (pinfunction "42_42") (pintype "passive"))
      (node (ref "J4") (pin "44") (pinfunction "44_44") (pintype "passive"))
      (node (ref "J4") (pin "46") (pinfunction "46_46") (pintype "passive"))
      (node (ref "J4") (pin "48") (pinfunction "48_48") (pintype "passive"))
      (node (ref "J4") (pin "50") (pinfunction "50_50") (pintype "passive"))
      (node (ref "J4") (pin "52") (pinfunction "52_52") (pintype "passive"))
      (node (ref "J4") (pin "54") (pinfunction "54_54") (pintype "passive"))
      (node (ref "J4") (pin "56") (pinfunction "56_56") (pintype "passive"))
      (node (ref "J4") (pin "58") (pinfunction "58_58") (pintype "passive"))
      (node (ref "J4") (pin "6") (pinfunction "6_6") (pintype "passive"))
      (node (ref "J4") (pin "62") (pinfunction "62_62") (pintype "passive"))
      (node (ref "J4") (pin "64") (pinfunction "64_64") (pintype "passive"))
      (node (ref "J4") (pin "66") (pinfunction "66_66") (pintype "passive"))
      (node (ref "J4") (pin "68") (pinfunction "68_68") (pintype "passive"))
      (node (ref "J4") (pin "8") (pinfunction "8_8") (pintype "passive"))
      (node (ref "J5") (pin "10") (pinfunction "10_10") (pintype "passive"))
      (node (ref "J5") (pin "12") (pinfunction "12_12") (pintype "passive"))
      (node (ref "J5") (pin "14") (pinfunction "14_14") (pintype "passive"))
      (node (ref "J5") (pin "16") (pinfunction "16_16") (pintype "passive"))
      (node (ref "J5") (pin "18") (pinfunction "18_18") (pintype "passive"))
      (node (ref "J5") (pin "2") (pinfunction "2_2") (pintype "passive"))
      (node (ref "J5") (pin "20") (pinfunction "20_20") (pintype "passive"))
      (node (ref "J5") (pin "22") (pinfunction "22_22") (pintype "passive"))
      (node (ref "J5") (pin "24") (pinfunction "24_24") (pintype "passive"))
      (node (ref "J5") (pin "26") (pinfunction "26_26") (pintype "passive"))
      (node (ref "J5") (pin "28") (pinfunction "28_28") (pintype "passive"))
      (node (ref "J5") (pin "32") (pinfunction "32_32") (pintype "passive"))
      (node (ref "J5") (pin "34") (pinfunction "34_34") (pintype "passive"))
      (node (ref "J5") (pin "36") (pinfunction "36_36") (pintype "passive"))
      (node (ref "J5") (pin "38") (pinfunction "38_38") (pintype "passive"))
      (node (ref "J5") (pin "4") (pinfunction "4_4") (pintype "passive"))
      (node (ref "J5") (pin "40") (pinfunction "40_40") (pintype "passive"))
      (node (ref "J5") (pin "42") (pinfunction "42_42") (pintype "passive"))
      (node (ref "J5") (pin "44") (pinfunction "44_44") (pintype "passive"))
      (node (ref "J5") (pin "46") (pinfunction "46_46") (pintype "passive"))
      (node (ref "J5") (pin "48") (pinfunction "48_48") (pintype "passive"))
      (node (ref "J5") (pin "50") (pinfunction "50_50") (pintype "passive"))
      (node (ref "J5") (pin "52") (pinfunction "52_52") (pintype "passive"))
      (node (ref "J5") (pin "54") (pinfunction "54_54") (pintype "passive"))
      (node (ref "J5") (pin "56") (pinfunction "56_56") (pintype "passive"))
      (node (ref "J5") (pin "58") (pinfunction "58_58") (pintype "passive"))
      (node (ref "J5") (pin "6") (pinfunction "6_6") (pintype "passive"))
      (node (ref "J5") (pin "62") (pinfunction "62_62") (pintype "passive"))
      (node (ref "J5") (pin "64") (pinfunction "64_64") (pintype "passive"))
      (node (ref "J5") (pin "66") (pinfunction "66_66") (pintype "passive"))
      (node (ref "J5") (pin "68") (pinfunction "68_68") (pintype "passive"))
      (node (ref "J5") (pin "8") (pinfunction "8_8") (pintype "passive"))
      (node (ref "J6") (pin "10") (pinfunction "10_10") (pintype "passive"))
      (node (ref "J6") (pin "12") (pinfunction "12_12") (pintype "passive"))
      (node (ref "J6") (pin "14") (pinfunction "14_14") (pintype "passive"))
      (node (ref "J6") (pin "16") (pinfunction "16_16") (pintype "passive"))
      (node (ref "J6") (pin "18") (pinfunction "18_18") (pintype "passive"))
      (node (ref "J6") (pin "2") (pinfunction "2_2") (pintype "passive"))
      (node (ref "J6") (pin "20") (pinfunction "20_20") (pintype "passive"))
      (node (ref "J6") (pin "22") (pinfunction "22_22") (pintype "passive"))
      (node (ref "J6") (pin "24") (pinfunction "24_24") (pintype "passive"))
      (node (ref "J6") (pin "26") (pinfunction "26_26") (pintype "passive"))
      (node (ref "J6") (pin "28") (pinfunction "28_28") (pintype "passive"))
      (node (ref "J6") (pin "32") (pinfunction "32_32") (pintype "passive"))
      (node (ref "J6") (pin "34") (pinfunction "34_34") (pintype "passive"))
      (node (ref "J6") (pin "36") (pinfunction "36_36") (pintype "passive"))
      (node (ref "J6") (pin "38") (pinfunction "38_38") (pintype "passive"))
      (node (ref "J6") (pin "4") (pinfunction "4_4") (pintype "passive"))
      (node (ref "J6") (pin "40") (pinfunction "40_40") (pintype "passive"))
      (node (ref "J6") (pin "42") (pinfunction "42_42") (pintype "passive"))
      (node (ref "J6") (pin "44") (pinfunction "44_44") (pintype "passive"))
      (node (ref "J6") (pin "46") (pinfunction "46_46") (pintype "passive"))
      (node (ref "J6") (pin "48") (pinfunction "48_48") (pintype "passive"))
      (node (ref "J6") (pin "50") (pinfunction "50_50") (pintype "passive"))
      (node (ref "J6") (pin "52") (pinfunction "52_52") (pintype "passive"))
      (node (ref "J6") (pin "54") (pinfunction "54_54") (pintype "passive"))
      (node (ref "J6") (pin "56") (pinfunction "56_56") (pintype "passive"))
      (node (ref "J6") (pin "58") (pinfunction "58_58") (pintype "passive"))
      (node (ref "J6") (pin "6") (pinfunction "6_6") (pintype "passive"))
      (node (ref "J6") (pin "62") (pinfunction "62_62") (pintype "passive"))
      (node (ref "J6") (pin "64") (pinfunction "64_64") (pintype "passive"))
      (node (ref "J6") (pin "66") (pinfunction "66_66") (pintype "passive"))
      (node (ref "J6") (pin "68") (pinfunction "68_68") (pintype "passive"))
      (node (ref "J6") (pin "8") (pinfunction "8_8") (pintype "passive"))
    )
    (net (code "201") (name "VDD") (class "Default")
      (node (ref "J6") (pin "51") (pinfunction "51_51") (pintype "passive"))
    )
    (net (code "202") (name "unconnected-(J1-PadMH1)") (class "Default")
      (node (ref "J1") (pin "MH1") (pinfunction "MH1_MH1") (pintype "passive"))
    )
    (net (code "203") (name "unconnected-(J1-PadMH2)") (class "Default")
      (node (ref "J1") (pin "MH2") (pinfunction "MH2_MH2") (pintype "passive"))
    )
    (net (code "204") (name "unconnected-(J1-PadMP1)") (class "Default")
      (node (ref "J1") (pin "MP1") (pinfunction "MP1_MP1") (pintype "passive"))
    )
    (net (code "205") (name "unconnected-(J1-PadMP2)") (class "Default")
      (node (ref "J1") (pin "MP2") (pinfunction "MP2_MP2") (pintype "passive"))
    )
    (net (code "206") (name "unconnected-(J2-PadMH1)") (class "Default")
      (node (ref "J2") (pin "MH1") (pinfunction "MH1_MH1") (pintype "passive"))
    )
    (net (code "207") (name "unconnected-(J2-PadMH2)") (class "Default")
      (node (ref "J2") (pin "MH2") (pinfunction "MH2_MH2") (pintype "passive"))
    )
    (net (code "208") (name "unconnected-(J2-PadMP1)") (class "Default")
      (node (ref "J2") (pin "MP1") (pinfunction "MP1_MP1") (pintype "passive"))
    )
    (net (code "209") (name "unconnected-(J2-PadMP2)") (class "Default")
      (node (ref "J2") (pin "MP2") (pinfunction "MP2_MP2") (pintype "passive"))
    )
    (net (code "210") (name "unconnected-(J3-Pad51)") (class "Default")
      (node (ref "J3") (pin "51") (pinfunction "51_51") (pintype "passive"))
    )
    (net (code "211") (name "unconnected-(J3-PadMH1)") (class "Default")
      (node (ref "J3") (pin "MH1") (pinfunction "MH1_MH1") (pintype "passive"))
    )
    (net (code "212") (name "unconnected-(J3-PadMH2)") (class "Default")
      (node (ref "J3") (pin "MH2") (pinfunction "MH2_MH2") (pintype "passive"))
    )
    (net (code "213") (name "unconnected-(J3-PadMP1)") (class "Default")
      (node (ref "J3") (pin "MP1") (pinfunction "MP1_MP1") (pintype "passive"))
    )
    (net (code "214") (name "unconnected-(J3-PadMP2)") (class "Default")
      (node (ref "J3") (pin "MP2") (pinfunction "MP2_MP2") (pintype "passive"))
    )
    (net (code "215") (name "unconnected-(J4-PadMH1)") (class "Default")
      (node (ref "J4") (pin "MH1") (pinfunction "MH1_MH1") (pintype "passive"))
    )
    (net (code "216") (name "unconnected-(J4-PadMH2)") (class "Default")
      (node (ref "J4") (pin "MH2") (pinfunction "MH2_MH2") (pintype "passive"))
    )
    (net (code "217") (name "unconnected-(J4-PadMP1)") (class "Default")
      (node (ref "J4") (pin "MP1") (pinfunction "MP1_MP1") (pintype "passive"))
    )
    (net (code "218") (name "unconnected-(J4-PadMP2)") (class "Default")
      (node (ref "J4") (pin "MP2") (pinfunction "MP2_MP2") (pintype "passive"))
    )
    (net (code "219") (name "unconnected-(J5-PadMH1)") (class "Default")
      (node (ref "J5") (pin "MH1") (pinfunction "MH1_MH1") (pintype "passive"))
    )
    (net (code "220") (name "unconnected-(J5-PadMH2)") (class "Default")
      (node (ref "J5") (pin "MH2") (pinfunction "MH2_MH2") (pintype "passive"))
    )
    (net (code "221") (name "unconnected-(J5-PadMP1)") (class "Default")
      (node (ref "J5") (pin "MP1") (pinfunction "MP1_MP1") (pintype "passive"))
    )
    (net (code "222") (name "unconnected-(J5-PadMP2)") (class "Default")
      (node (ref "J5") (pin "MP2") (pinfunction "MP2_MP2") (pintype "passive"))
    )
    (net (code "223") (name "unconnected-(J6-PadMH1)") (class "Default")
      (node (ref "J6") (pin "MH1") (pinfunction "MH1_MH1") (pintype "passive"))
    )
    (net (code "224") (name "unconnected-(J6-PadMH2)") (class "Default")
      (node (ref "J6") (pin "MH2") (pinfunction "MH2_MH2") (pintype "passive"))
    )
    (net (code "225") (name "unconnected-(J6-PadMP1)") (class "Default")
      (node (ref "J6") (pin "MP1") (pinfunction "MP1_MP1") (pintype "passive"))
    )
    (net (code "226") (name "unconnected-(J6-PadMP2)") (class "Default")
      (node (ref "J6") (pin "MP2") (pinfunction "MP2_MP2") (pintype "passive"))
    )
  )
)
